# TopPCB-011113.net
KiCad netlist of a schematic drawn in EAGLE
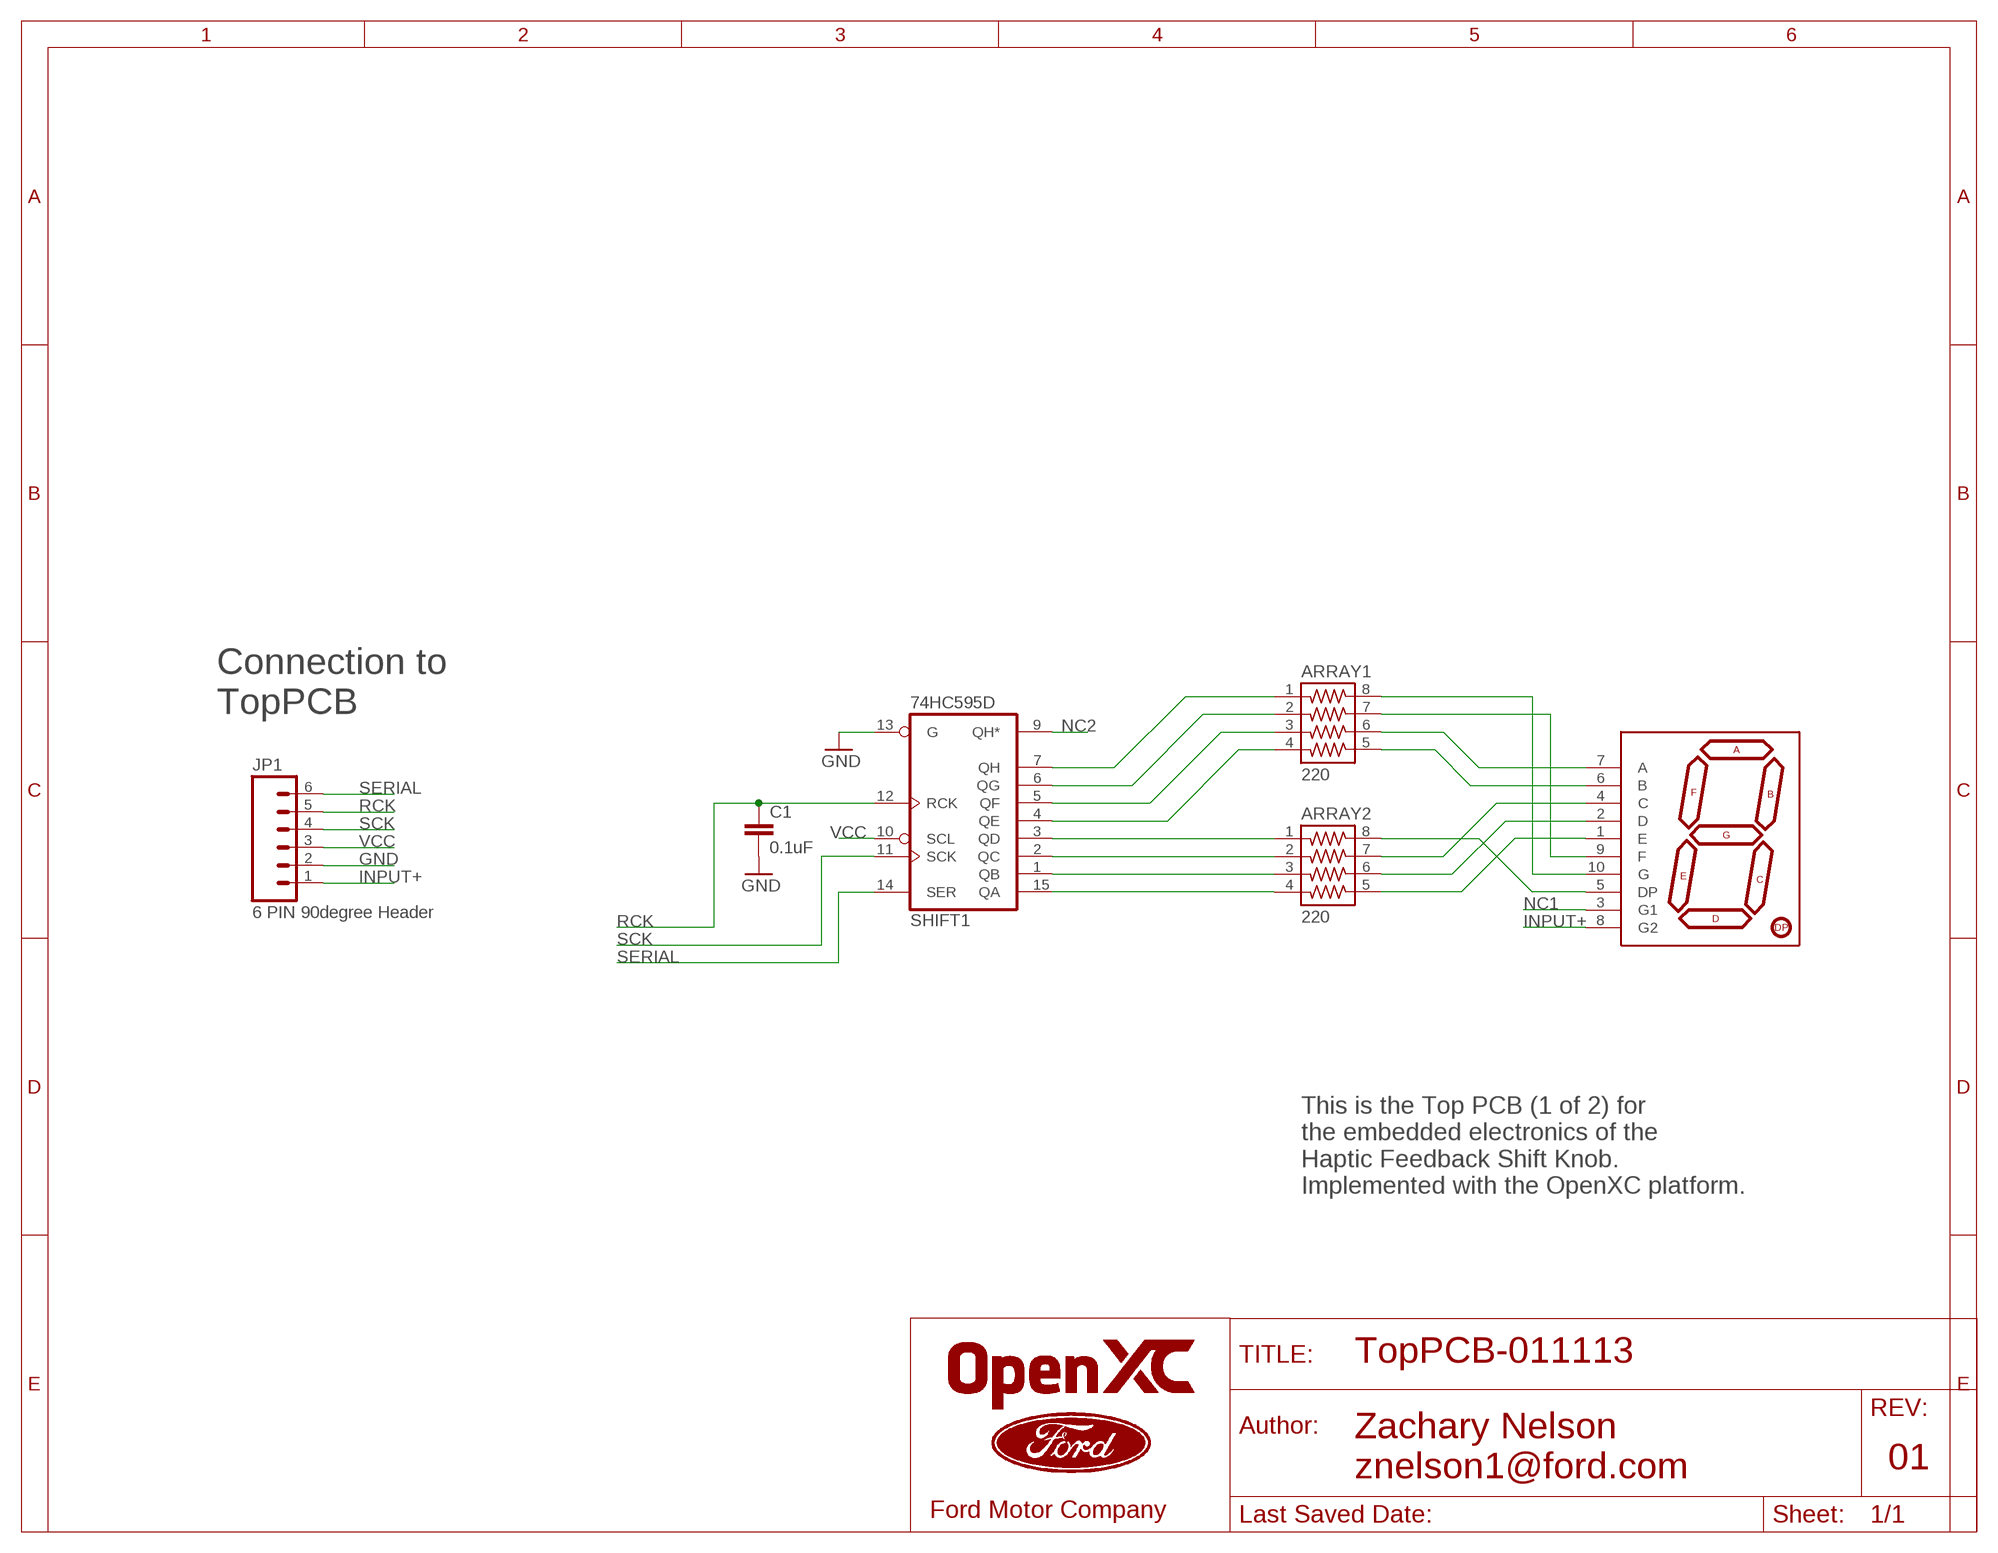
[diagram p0: schematic, sheet 1]

(export (version "E")
  (design (tool "Eeschema 10.0.6"))
  (components
    (comp (ref "7SEGMENT")
      (value "7-SEGMENT-DISPLAY-1\"-RED")
      (footprint "eagle-import:7-SEGMENT-1_PTH")
      (libsource (lib "eagle-import") (part "7-SEGMENT-DISPLAY-1{dblquote}-RED"))
    )
    (comp (ref "ARRAY1")
      (value "220")
      (footprint "eagle-import:744-8")
      (libsource (lib "eagle-import") (part "744-8"))
    )
    (comp (ref "ARRAY2")
      (value "220")
      (footprint "eagle-import:744-8")
      (libsource (lib "eagle-import") (part "744-8"))
    )
    (comp (ref "C1")
      (value "0.1uF")
      (footprint "eagle-import:0402-CAP")
      (libsource (lib "eagle-import") (part "CAP0402-CAP"))
    )
    (comp (ref "JP1")
      (value "6 PIN 90degree Header")
      (footprint "eagle-import:1X06")
      (libsource (lib "eagle-import") (part "M06SIP"))
    )
    (comp (ref "SHIFT1")
      (value "74HC595D")
      (footprint "eagle-import:SO16")
      (libsource (lib "eagle-import") (part "74595DHC"))
    )
  )
  (nets
    (net (code "1") (name "/INPUT+") (class "Default")
      (node (ref "7SEGMENT") (pin "8") (pinfunction "G2_8") (pintype "bidirectional"))
      (node (ref "JP1") (pin "1") (pinfunction "1_1") (pintype "passive"))
    )
    (net (code "2") (name "/NC1") (class "Default")
      (node (ref "7SEGMENT") (pin "3") (pinfunction "G1_3") (pintype "bidirectional"))
    )
    (net (code "3") (name "/NC2") (class "Default")
      (node (ref "SHIFT1") (pin "9") (pinfunction "QH*_9") (pintype "tri_state"))
    )
    (net (code "4") (name "/RCK") (class "Default")
      (node (ref "C1") (pin "1") (pinfunction "1_1") (pintype "passive"))
      (node (ref "JP1") (pin "5") (pinfunction "5_5") (pintype "passive"))
      (node (ref "SHIFT1") (pin "12") (pinfunction "RCK_12") (pintype "input"))
    )
    (net (code "5") (name "/SCK") (class "Default")
      (node (ref "JP1") (pin "4") (pinfunction "4_4") (pintype "passive"))
      (node (ref "SHIFT1") (pin "11") (pinfunction "SCK_11") (pintype "input"))
    )
    (net (code "6") (name "/SERIAL") (class "Default")
      (node (ref "JP1") (pin "6") (pinfunction "6_6") (pintype "passive"))
      (node (ref "SHIFT1") (pin "14") (pinfunction "SER_14") (pintype "input"))
    )
    (net (code "7") (name "/VCC") (class "Default")
      (node (ref "JP1") (pin "3") (pinfunction "3_3") (pintype "passive"))
      (node (ref "SHIFT1") (pin "10") (pinfunction "SCL_10") (pintype "input"))
    )
    (net (code "8") (name "GND") (class "Default")
      (node (ref "C1") (pin "2") (pinfunction "2_2") (pintype "passive"))
      (node (ref "JP1") (pin "2") (pinfunction "2_2") (pintype "passive"))
      (node (ref "SHIFT1") (pin "13") (pinfunction "G_13") (pintype "input"))
    )
    (net (code "9") (name "Net-(7SEGMENT-A)") (class "Default")
      (node (ref "7SEGMENT") (pin "7") (pinfunction "A_7") (pintype "bidirectional"))
      (node (ref "ARRAY1") (pin "6") (pinfunction "6_6") (pintype "passive"))
    )
    (net (code "10") (name "Net-(7SEGMENT-B)") (class "Default")
      (node (ref "7SEGMENT") (pin "6") (pinfunction "B_6") (pintype "bidirectional"))
      (node (ref "ARRAY1") (pin "5") (pinfunction "5_5") (pintype "passive"))
    )
    (net (code "11") (name "Net-(7SEGMENT-C)") (class "Default")
      (node (ref "7SEGMENT") (pin "4") (pinfunction "C_4") (pintype "bidirectional"))
      (node (ref "ARRAY2") (pin "7") (pinfunction "7_7") (pintype "passive"))
    )
    (net (code "12") (name "Net-(7SEGMENT-D)") (class "Default")
      (node (ref "7SEGMENT") (pin "2") (pinfunction "D_2") (pintype "bidirectional"))
      (node (ref "ARRAY2") (pin "6") (pinfunction "6_6") (pintype "passive"))
    )
    (net (code "13") (name "Net-(7SEGMENT-DP)") (class "Default")
      (node (ref "7SEGMENT") (pin "5") (pinfunction "DP_5") (pintype "bidirectional"))
      (node (ref "ARRAY2") (pin "8") (pinfunction "8_8") (pintype "passive"))
    )
    (net (code "14") (name "Net-(7SEGMENT-E)") (class "Default")
      (node (ref "7SEGMENT") (pin "1") (pinfunction "E_1") (pintype "bidirectional"))
      (node (ref "ARRAY2") (pin "5") (pinfunction "5_5") (pintype "passive"))
    )
    (net (code "15") (name "Net-(7SEGMENT-F)") (class "Default")
      (node (ref "7SEGMENT") (pin "9") (pinfunction "F_9") (pintype "bidirectional"))
      (node (ref "ARRAY1") (pin "7") (pinfunction "7_7") (pintype "passive"))
    )
    (net (code "16") (name "Net-(7SEGMENT-G)") (class "Default")
      (node (ref "7SEGMENT") (pin "10") (pinfunction "G_10") (pintype "bidirectional"))
      (node (ref "ARRAY1") (pin "8") (pinfunction "8_8") (pintype "passive"))
    )
    (net (code "17") (name "Net-(SHIFT1A-QA)") (class "Default")
      (node (ref "ARRAY2") (pin "4") (pinfunction "4_4") (pintype "passive"))
      (node (ref "SHIFT1") (pin "15") (pinfunction "QA_15") (pintype "tri_state"))
    )
    (net (code "18") (name "Net-(SHIFT1A-QB)") (class "Default")
      (node (ref "ARRAY2") (pin "3") (pinfunction "3_3") (pintype "passive"))
      (node (ref "SHIFT1") (pin "1") (pinfunction "QB_1") (pintype "tri_state"))
    )
    (net (code "19") (name "Net-(SHIFT1A-QC)") (class "Default")
      (node (ref "ARRAY2") (pin "2") (pinfunction "2_2") (pintype "passive"))
      (node (ref "SHIFT1") (pin "2") (pinfunction "QC_2") (pintype "tri_state"))
    )
    (net (code "20") (name "Net-(SHIFT1A-QD)") (class "Default")
      (node (ref "ARRAY2") (pin "1") (pinfunction "1_1") (pintype "passive"))
      (node (ref "SHIFT1") (pin "3") (pinfunction "QD_3") (pintype "tri_state"))
    )
    (net (code "21") (name "Net-(SHIFT1A-QE)") (class "Default")
      (node (ref "ARRAY1") (pin "4") (pinfunction "4_4") (pintype "passive"))
      (node (ref "SHIFT1") (pin "4") (pinfunction "QE_4") (pintype "tri_state"))
    )
    (net (code "22") (name "Net-(SHIFT1A-QF)") (class "Default")
      (node (ref "ARRAY1") (pin "3") (pinfunction "3_3") (pintype "passive"))
      (node (ref "SHIFT1") (pin "5") (pinfunction "QF_5") (pintype "tri_state"))
    )
    (net (code "23") (name "Net-(SHIFT1A-QG)") (class "Default")
      (node (ref "ARRAY1") (pin "2") (pinfunction "2_2") (pintype "passive"))
      (node (ref "SHIFT1") (pin "6") (pinfunction "QG_6") (pintype "tri_state"))
    )
    (net (code "24") (name "Net-(SHIFT1A-QH)") (class "Default")
      (node (ref "ARRAY1") (pin "1") (pinfunction "1_1") (pintype "passive"))
      (node (ref "SHIFT1") (pin "7") (pinfunction "QH_7") (pintype "tri_state"))
    )
  )
)
